# comms_sys_schematic_R2.net
KiCad netlist of a schematic drawn in EAGLE
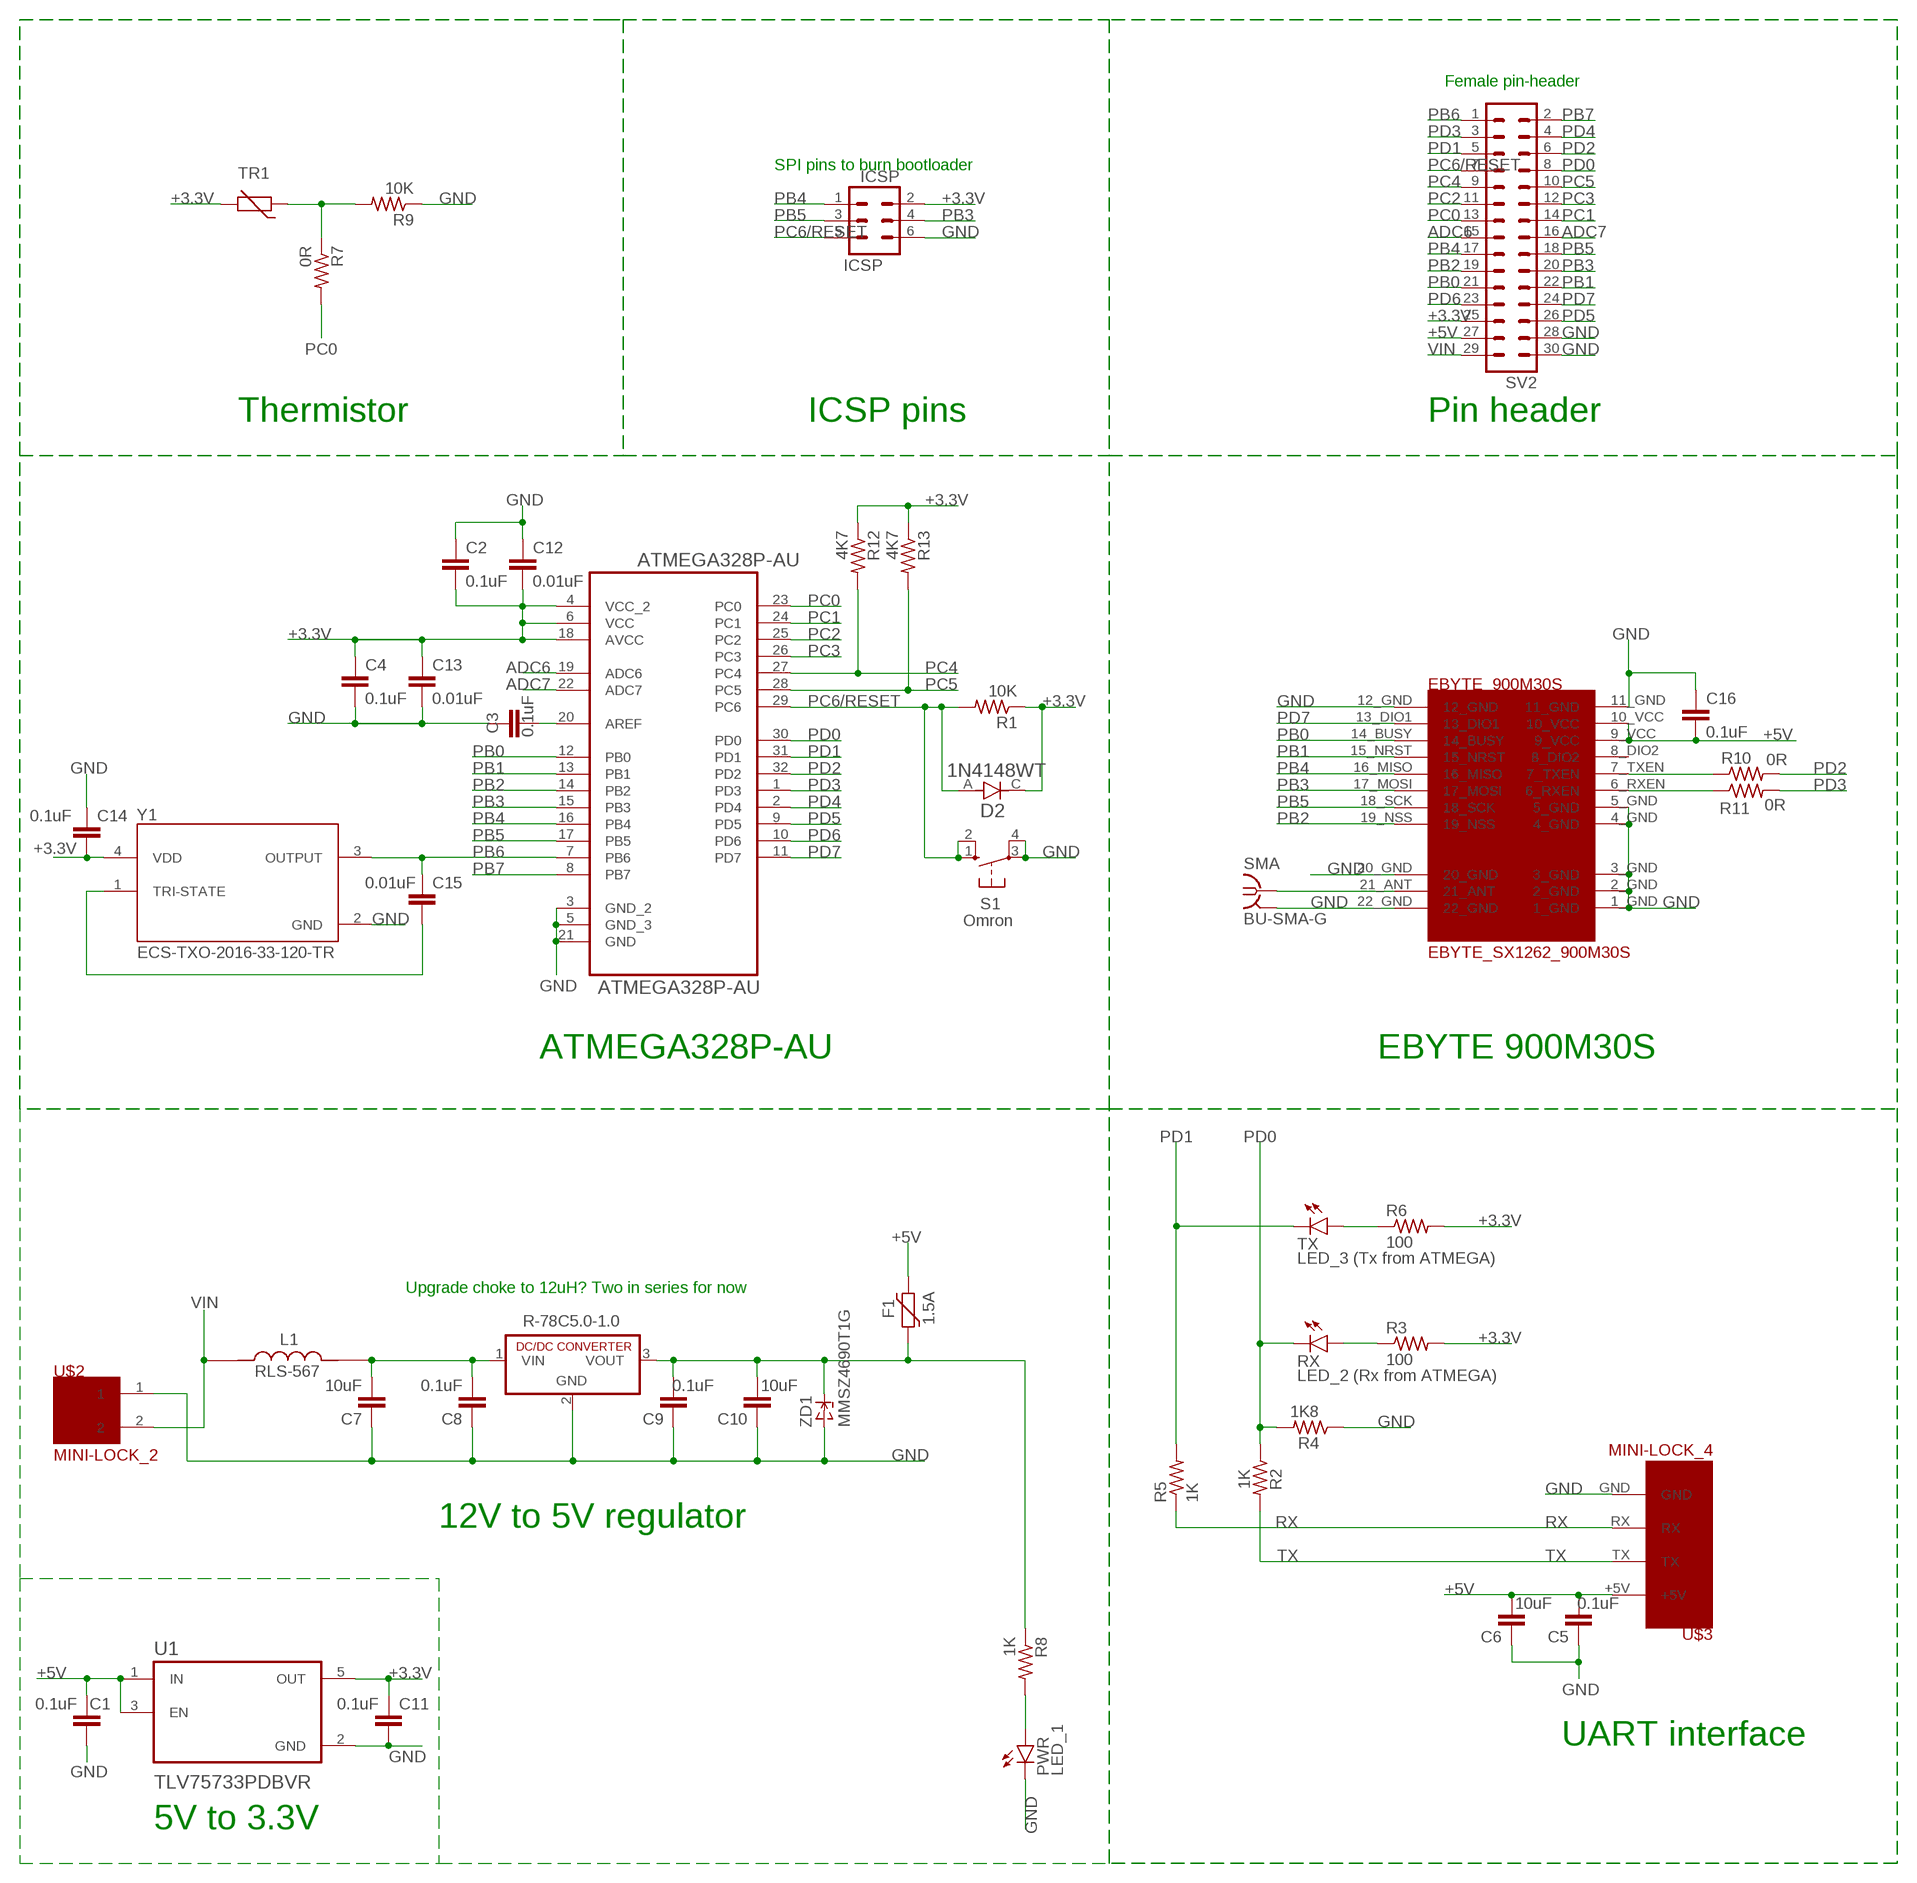
[diagram p0: schematic, sheet 1]

(export (version "E")
  (design (tool "Eeschema 10.0.6"))
  (components
    (comp (ref "ATMEGA328P-AU")
      (value "ATMEGA328P-AU")
      (footprint "eagle-import:QFP80P900X900X120-32N")
      (libsource (lib "eagle-import") (part "ATMEGA328P-AU"))
    )
    (comp (ref "C1")
      (value "0.1uF")
      (footprint "eagle-import:C0805")
      (libsource (lib "eagle-import") (part "C-EUC0805"))
    )
    (comp (ref "C2")
      (value "0.1uF")
      (footprint "eagle-import:C0805")
      (libsource (lib "eagle-import") (part "C-EUC0805"))
    )
    (comp (ref "C3")
      (value "0.1uF")
      (footprint "eagle-import:C0805")
      (libsource (lib "eagle-import") (part "C-EUC0805"))
    )
    (comp (ref "C4")
      (value "0.1uF")
      (footprint "eagle-import:C0805")
      (libsource (lib "eagle-import") (part "C-EUC0805"))
    )
    (comp (ref "C5")
      (value "0.1uF")
      (footprint "eagle-import:C0805")
      (libsource (lib "eagle-import") (part "C-EUC0805"))
    )
    (comp (ref "C6")
      (value "10uF")
      (footprint "eagle-import:C0805")
      (libsource (lib "eagle-import") (part "C-EUC0805"))
    )
    (comp (ref "C7")
      (value "10uF")
      (footprint "eagle-import:C0805")
      (libsource (lib "eagle-import") (part "C-EUC0805"))
    )
    (comp (ref "C8")
      (value "0.1uF")
      (footprint "eagle-import:C0805")
      (libsource (lib "eagle-import") (part "C-EUC0805"))
    )
    (comp (ref "C9")
      (value "0.1uF")
      (footprint "eagle-import:C0805")
      (libsource (lib "eagle-import") (part "C-EUC0805"))
    )
    (comp (ref "C10")
      (value "10uF")
      (footprint "eagle-import:C0805")
      (libsource (lib "eagle-import") (part "C-EUC0805"))
    )
    (comp (ref "C11")
      (value "0.1uF")
      (footprint "eagle-import:C0805")
      (libsource (lib "eagle-import") (part "C-EUC0805"))
    )
    (comp (ref "C12")
      (value "0.01uF")
      (footprint "eagle-import:C0805")
      (libsource (lib "eagle-import") (part "C-EUC0805"))
    )
    (comp (ref "C13")
      (value "0.01uF")
      (footprint "eagle-import:C0805")
      (libsource (lib "eagle-import") (part "C-EUC0805"))
    )
    (comp (ref "C14")
      (value "0.1uF")
      (footprint "eagle-import:C0805")
      (libsource (lib "eagle-import") (part "C-EUC0805"))
    )
    (comp (ref "C15")
      (value "0.01uF")
      (footprint "eagle-import:C0805")
      (libsource (lib "eagle-import") (part "C-EUC0805"))
    )
    (comp (ref "C16")
      (value "0.1uF")
      (footprint "eagle-import:C0805")
      (libsource (lib "eagle-import") (part "C-EUC0805"))
    )
    (comp (ref "D2")
      (value "1N4148WT")
      (footprint "eagle-import:SODFL1608X70N")
      (fields (field (name "DIGI-KEY_PART_NUMBER") "1N4148WTCT-ND") (field (name "MF") "ON Semiconductor"))
      (libsource (lib "eagle-import") (part "1N4148WT"))
    )
    (comp (ref "EBYTE_900M30S")
      (value "EBYTE_SX1262_900M30S")
      (footprint "eagle-import:EBYTE_SX1262_900M30S_FOOTPRINT")
      (libsource (lib "eagle-import") (part "EBYTE_SX1262_900M30S"))
    )
    (comp (ref "F1")
      (value "1.5A")
      (footprint "eagle-import:PTC0805")
      (libsource (lib "eagle-import") (part "FUSE_PTC-0805"))
    )
    (comp (ref "ICSP")
      (value "ICSP")
      (footprint "eagle-import:MA03-2")
      (libsource (lib "eagle-import") (part "MA03-2"))
    )
    (comp (ref "L1")
      (value "RLS-567")
      (footprint "eagle-import:IND_RLS-567")
      (fields (field (name "MF") "Recom Power"))
      (libsource (lib "eagle-import") (part "RLS-567"))
    )
    (comp (ref "PWR")
      (value "LED_1")
      (footprint "eagle-import:CHIP-LED0805")
      (libsource (lib "eagle-import") (part "LEDCHIP-LED0805"))
    )
    (comp (ref "R-78C5.0-1.0")
      (value "R-78C5.0-1.0")
      (footprint "eagle-import:SIP3")
      (libsource (lib "eagle-import") (part "R-78C-1.05.0"))
    )
    (comp (ref "R1")
      (value "10K")
      (footprint "eagle-import:R0805")
      (libsource (lib "eagle-import") (part "R-US_R0805"))
    )
    (comp (ref "R2")
      (value "1K")
      (footprint "eagle-import:R0805")
      (libsource (lib "eagle-import") (part "R-US_R0805"))
    )
    (comp (ref "R3")
      (value "100")
      (footprint "eagle-import:R0805")
      (libsource (lib "eagle-import") (part "R-US_R0805"))
    )
    (comp (ref "R4")
      (value "1K8")
      (footprint "eagle-import:R0805")
      (libsource (lib "eagle-import") (part "R-US_R0805"))
    )
    (comp (ref "R5")
      (value "1K")
      (footprint "eagle-import:R0805")
      (libsource (lib "eagle-import") (part "R-US_R0805"))
    )
    (comp (ref "R6")
      (value "100")
      (footprint "eagle-import:R0805")
      (libsource (lib "eagle-import") (part "R-US_R0805"))
    )
    (comp (ref "R7")
      (value "0R")
      (footprint "eagle-import:R0805")
      (libsource (lib "eagle-import") (part "R-US_R0805"))
    )
    (comp (ref "R8")
      (value "1K")
      (footprint "eagle-import:R0805")
      (libsource (lib "eagle-import") (part "R-US_R0805"))
    )
    (comp (ref "R9")
      (value "10K")
      (footprint "eagle-import:R0805")
      (libsource (lib "eagle-import") (part "R-US_R0805"))
    )
    (comp (ref "R10")
      (value "0R")
      (footprint "eagle-import:R0805")
      (libsource (lib "eagle-import") (part "R-US_R0805"))
    )
    (comp (ref "R11")
      (value "0R")
      (footprint "eagle-import:R0805")
      (libsource (lib "eagle-import") (part "R-US_R0805"))
    )
    (comp (ref "R12")
      (value "4K7")
      (footprint "eagle-import:R0805")
      (libsource (lib "eagle-import") (part "R-US_R0805"))
    )
    (comp (ref "R13")
      (value "4K7")
      (footprint "eagle-import:R0805")
      (libsource (lib "eagle-import") (part "R-US_R0805"))
    )
    (comp (ref "RX")
      (value "LED_2 (Rx from ATMEGA)")
      (footprint "eagle-import:CHIP-LED0805")
      (libsource (lib "eagle-import") (part "LEDCHIP-LED0805"))
    )
    (comp (ref "S1")
      (value "Omron")
      (footprint "eagle-import:B3F-10XX")
      (fields (field (name "MPN") "B3F-1000"))
      (libsource (lib "eagle-import") (part "10-XX"))
    )
    (comp (ref "SMA")
      (value "BU-SMA-G")
      (footprint "eagle-import:BU-SMA-G")
      (libsource (lib "eagle-import") (part "BU-SMA-G"))
    )
    (comp (ref "SV2")
      (value "MA15-2")
      (footprint "eagle-import:MA15-2")
      (libsource (lib "eagle-import") (part "MA15-2"))
    )
    (comp (ref "TR1")
      (value "THERMISTOR_R-2,5")
      (footprint "eagle-import:RS-2,5")
      (libsource (lib "eagle-import") (part "THERMISTOR_R-2,5"))
    )
    (comp (ref "TX")
      (value "LED_3 (Tx from ATMEGA)")
      (footprint "eagle-import:CHIP-LED0805")
      (libsource (lib "eagle-import") (part "LEDCHIP-LED0805"))
    )
    (comp (ref "U$2")
      (value "MINI-LOCK_2")
      (footprint "eagle-import:MINI-LOCK_2")
      (libsource (lib "eagle-import") (part "MINI-LOCK_2"))
    )
    (comp (ref "U$3")
      (value "MINI-LOCK_4")
      (footprint "eagle-import:MINI-LOCK_4")
      (libsource (lib "eagle-import") (part "MINI-LOCK_4"))
    )
    (comp (ref "U1")
      (value "TLV75733PDBVR")
      (footprint "eagle-import:SOT95P280X145-5N")
      (fields (field (name "DIGI-KEY_PART_NUMBER") "296-50414-1-ND") (field (name "MF") "Texas Instruments"))
      (libsource (lib "eagle-import") (part "TLV75733PDBVR"))
    )
    (comp (ref "Y1")
      (value "ECS-TXO-2016-33-120-TR")
      (footprint "eagle-import:OSC_ECS-TXO-2016-33-120-TR")
      (fields (field (name "DIGI-KEY_PART_NUMBER") "XC3160CT-ND") (field (name "MF") "ECS Inc."))
      (libsource (lib "eagle-import") (part "ECS-TXO-2016-33-120-TR"))
    )
    (comp (ref "ZD1")
      (value "MMSZ4690T1G")
      (footprint "eagle-import:SOD-123")
      (libsource (lib "eagle-import") (part "ZENERSOD-123"))
    )
  )
  (nets
    (net (code "1") (name "/+3.3V") (class "Default")
      (node (ref "ATMEGA328P-AU") (pin "18") (pinfunction "AVCC_18") (pintype "power_in"))
      (node (ref "ATMEGA328P-AU") (pin "4") (pinfunction "VCC_2_4") (pintype "power_in"))
      (node (ref "ATMEGA328P-AU") (pin "6") (pinfunction "VCC_6") (pintype "power_in"))
      (node (ref "C11") (pin "2") (pinfunction "2_2") (pintype "passive"))
      (node (ref "C12") (pin "2") (pinfunction "2_2") (pintype "passive"))
      (node (ref "C13") (pin "1") (pinfunction "1_1") (pintype "passive"))
      (node (ref "C14") (pin "2") (pinfunction "2_2") (pintype "passive"))
      (node (ref "C2") (pin "2") (pinfunction "2_2") (pintype "passive"))
      (node (ref "C4") (pin "1") (pinfunction "1_1") (pintype "passive"))
      (node (ref "D2") (pin "C") (pinfunction "C_C") (pintype "passive"))
      (node (ref "ICSP") (pin "2") (pinfunction "2_2") (pintype "passive"))
      (node (ref "R1") (pin "1") (pinfunction "1_1") (pintype "passive"))
      (node (ref "R12") (pin "1") (pinfunction "1_1") (pintype "passive"))
      (node (ref "R13") (pin "1") (pinfunction "1_1") (pintype "passive"))
      (node (ref "R3") (pin "2") (pinfunction "2_2") (pintype "passive"))
      (node (ref "R6") (pin "2") (pinfunction "2_2") (pintype "passive"))
      (node (ref "SV2") (pin "25") (pinfunction "29_25") (pintype "passive"))
      (node (ref "TR1") (pin "2") (pinfunction "2_2") (pintype "passive"))
      (node (ref "U1") (pin "5") (pinfunction "OUT_5") (pintype "output"))
      (node (ref "Y1") (pin "4") (pinfunction "VDD_4") (pintype "input"))
    )
    (net (code "2") (name "/+5V") (class "Default")
      (node (ref "C1") (pin "2") (pinfunction "2_2") (pintype "passive"))
      (node (ref "C16") (pin "2") (pinfunction "2_2") (pintype "passive"))
      (node (ref "C5") (pin "2") (pinfunction "2_2") (pintype "passive"))
      (node (ref "C6") (pin "2") (pinfunction "2_2") (pintype "passive"))
      (node (ref "EBYTE_900M30S") (pin "10_VCC") (pinfunction "10_VCC_10_VCC") (pintype "power_in"))
      (node (ref "EBYTE_900M30S") (pin "9_VCC") (pinfunction "9_VCC_9_VCC") (pintype "power_in"))
      (node (ref "F1") (pin "2") (pinfunction "2_2") (pintype "passive"))
      (node (ref "SV2") (pin "27") (pinfunction "31_27") (pintype "passive"))
      (node (ref "U$3") (pin "+5V") (pinfunction "+5V_+5V") (pintype "bidirectional"))
      (node (ref "U1") (pin "1") (pinfunction "IN_1") (pintype "input"))
      (node (ref "U1") (pin "3") (pinfunction "EN_3") (pintype "bidirectional"))
    )
    (net (code "3") (name "/ADC6") (class "Default")
      (node (ref "ATMEGA328P-AU") (pin "19") (pinfunction "ADC6_19") (pintype "input"))
      (node (ref "SV2") (pin "15") (pinfunction "19_15") (pintype "passive"))
    )
    (net (code "4") (name "/ADC7") (class "Default")
      (node (ref "ATMEGA328P-AU") (pin "22") (pinfunction "ADC7_22") (pintype "input"))
      (node (ref "SV2") (pin "16") (pinfunction "20_16") (pintype "passive"))
    )
    (net (code "5") (name "/GND") (class "Default")
      (node (ref "ATMEGA328P-AU") (pin "21") (pinfunction "GND_21") (pintype "passive"))
      (node (ref "ATMEGA328P-AU") (pin "3") (pinfunction "GND_2_3") (pintype "passive"))
      (node (ref "ATMEGA328P-AU") (pin "5") (pinfunction "GND_3_5") (pintype "passive"))
      (node (ref "C1") (pin "1") (pinfunction "1_1") (pintype "passive"))
      (node (ref "C10") (pin "1") (pinfunction "1_1") (pintype "passive"))
      (node (ref "C11") (pin "1") (pinfunction "1_1") (pintype "passive"))
      (node (ref "C12") (pin "1") (pinfunction "1_1") (pintype "passive"))
      (node (ref "C13") (pin "2") (pinfunction "2_2") (pintype "passive"))
      (node (ref "C14") (pin "1") (pinfunction "1_1") (pintype "passive"))
      (node (ref "C16") (pin "1") (pinfunction "1_1") (pintype "passive"))
      (node (ref "C2") (pin "1") (pinfunction "1_1") (pintype "passive"))
      (node (ref "C3") (pin "1") (pinfunction "1_1") (pintype "passive"))
      (node (ref "C4") (pin "2") (pinfunction "2_2") (pintype "passive"))
      (node (ref "C5") (pin "1") (pinfunction "1_1") (pintype "passive"))
      (node (ref "C6") (pin "1") (pinfunction "1_1") (pintype "passive"))
      (node (ref "C7") (pin "1") (pinfunction "1_1") (pintype "passive"))
      (node (ref "C8") (pin "1") (pinfunction "1_1") (pintype "passive"))
      (node (ref "C9") (pin "1") (pinfunction "1_1") (pintype "passive"))
      (node (ref "EBYTE_900M30S") (pin "11_GND") (pinfunction "11_GND_11_GND") (pintype "power_in"))
      (node (ref "EBYTE_900M30S") (pin "12_GND") (pinfunction "12_GND_12_GND") (pintype "power_in"))
      (node (ref "EBYTE_900M30S") (pin "1_GND") (pinfunction "1_GND_1_GND") (pintype "power_in"))
      (node (ref "EBYTE_900M30S") (pin "20_GND") (pinfunction "20_GND_20_GND") (pintype "power_in"))
      (node (ref "EBYTE_900M30S") (pin "22_GND") (pinfunction "22_GND_22_GND") (pintype "power_in"))
      (node (ref "EBYTE_900M30S") (pin "2_GND") (pinfunction "2_GND_2_GND") (pintype "power_in"))
      (node (ref "EBYTE_900M30S") (pin "3_GND") (pinfunction "3_GND_3_GND") (pintype "power_in"))
      (node (ref "EBYTE_900M30S") (pin "4_GND") (pinfunction "4_GND_4_GND") (pintype "power_in"))
      (node (ref "EBYTE_900M30S") (pin "5_GND") (pinfunction "5_GND_5_GND") (pintype "power_in"))
      (node (ref "ICSP") (pin "6") (pinfunction "6_6") (pintype "passive"))
      (node (ref "PWR") (pin "C") (pinfunction "C_C") (pintype "passive"))
      (node (ref "R-78C5.0-1.0") (pin "2") (pinfunction "GND_2") (pintype "passive"))
      (node (ref "R4") (pin "1") (pinfunction "1_1") (pintype "passive"))
      (node (ref "R9") (pin "1") (pinfunction "1_1") (pintype "passive"))
      (node (ref "S1") (pin "3") (pinfunction "P_3") (pintype "passive"))
      (node (ref "S1") (pin "4") (pinfunction "P1_4") (pintype "passive"))
      (node (ref "SMA") (pin "2") (pinfunction "2_2") (pintype "passive"))
      (node (ref "SMA") (pin "3") (pinfunction "2_3") (pintype "passive"))
      (node (ref "SMA") (pin "4") (pinfunction "2_4") (pintype "passive"))
      (node (ref "SMA") (pin "5") (pinfunction "2_5") (pintype "passive"))
      (node (ref "SV2") (pin "28") (pinfunction "32_28") (pintype "passive"))
      (node (ref "SV2") (pin "30") (pinfunction "34_30") (pintype "passive"))
      (node (ref "U$2") (pin "1") (pinfunction "1_1") (pintype "bidirectional"))
      (node (ref "U$3") (pin "GND") (pinfunction "GND_GND") (pintype "bidirectional"))
      (node (ref "U1") (pin "2") (pinfunction "GND_2") (pintype "power_in"))
      (node (ref "Y1") (pin "2") (pinfunction "GND_2") (pintype "power_in"))
      (node (ref "ZD1") (pin "A") (pinfunction "A_A") (pintype "passive"))
    )
    (net (code "6") (name "/PB0") (class "Default")
      (node (ref "ATMEGA328P-AU") (pin "12") (pinfunction "PB0_12") (pintype "bidirectional"))
      (node (ref "EBYTE_900M30S") (pin "14_BUSY") (pinfunction "14_BUSY_14_BUSY") (pintype "bidirectional"))
      (node (ref "SV2") (pin "21") (pinfunction "25_21") (pintype "passive"))
    )
    (net (code "7") (name "/PB1") (class "Default")
      (node (ref "ATMEGA328P-AU") (pin "13") (pinfunction "PB1_13") (pintype "bidirectional"))
      (node (ref "EBYTE_900M30S") (pin "15_NRST") (pinfunction "15_NRST_15_NRST") (pintype "bidirectional"))
      (node (ref "SV2") (pin "22") (pinfunction "26_22") (pintype "passive"))
    )
    (net (code "8") (name "/PB2") (class "Default")
      (node (ref "ATMEGA328P-AU") (pin "14") (pinfunction "PB2_14") (pintype "bidirectional"))
      (node (ref "EBYTE_900M30S") (pin "19_NSS") (pinfunction "19_NSS_19_NSS") (pintype "bidirectional"))
      (node (ref "SV2") (pin "19") (pinfunction "23_19") (pintype "passive"))
    )
    (net (code "9") (name "/PB3") (class "Default")
      (node (ref "ATMEGA328P-AU") (pin "15") (pinfunction "PB3_15") (pintype "bidirectional"))
      (node (ref "EBYTE_900M30S") (pin "17_MOSI") (pinfunction "17_MOSI_17_MOSI") (pintype "bidirectional"))
      (node (ref "ICSP") (pin "4") (pinfunction "4_4") (pintype "passive"))
      (node (ref "SV2") (pin "20") (pinfunction "24_20") (pintype "passive"))
    )
    (net (code "10") (name "/PB4") (class "Default")
      (node (ref "ATMEGA328P-AU") (pin "16") (pinfunction "PB4_16") (pintype "bidirectional"))
      (node (ref "EBYTE_900M30S") (pin "16_MISO") (pinfunction "16_MISO_16_MISO") (pintype "bidirectional"))
      (node (ref "ICSP") (pin "1") (pinfunction "1_1") (pintype "passive"))
      (node (ref "SV2") (pin "17") (pinfunction "21_17") (pintype "passive"))
    )
    (net (code "11") (name "/PB5") (class "Default")
      (node (ref "ATMEGA328P-AU") (pin "17") (pinfunction "PB5_17") (pintype "bidirectional"))
      (node (ref "EBYTE_900M30S") (pin "18_SCK") (pinfunction "18_SCK_18_SCK") (pintype "bidirectional"))
      (node (ref "ICSP") (pin "3") (pinfunction "3_3") (pintype "passive"))
      (node (ref "SV2") (pin "18") (pinfunction "22_18") (pintype "passive"))
    )
    (net (code "12") (name "/PB6") (class "Default")
      (node (ref "ATMEGA328P-AU") (pin "7") (pinfunction "PB6_7") (pintype "bidirectional"))
      (node (ref "C15") (pin "1") (pinfunction "1_1") (pintype "passive"))
      (node (ref "SV2") (pin "1") (pinfunction "5_1") (pintype "passive"))
      (node (ref "Y1") (pin "3") (pinfunction "OUTPUT_3") (pintype "output"))
    )
    (net (code "13") (name "/PB7") (class "Default")
      (node (ref "ATMEGA328P-AU") (pin "8") (pinfunction "PB7_8") (pintype "bidirectional"))
      (node (ref "SV2") (pin "2") (pinfunction "6_2") (pintype "passive"))
    )
    (net (code "14") (name "/PC0") (class "Default")
      (node (ref "ATMEGA328P-AU") (pin "23") (pinfunction "PC0_23") (pintype "bidirectional"))
      (node (ref "R7") (pin "2") (pinfunction "2_2") (pintype "passive"))
      (node (ref "SV2") (pin "13") (pinfunction "17_13") (pintype "passive"))
    )
    (net (code "15") (name "/PC1") (class "Default")
      (node (ref "ATMEGA328P-AU") (pin "24") (pinfunction "PC1_24") (pintype "bidirectional"))
      (node (ref "SV2") (pin "14") (pinfunction "18_14") (pintype "passive"))
    )
    (net (code "16") (name "/PC2") (class "Default")
      (node (ref "ATMEGA328P-AU") (pin "25") (pinfunction "PC2_25") (pintype "bidirectional"))
      (node (ref "SV2") (pin "11") (pinfunction "15_11") (pintype "passive"))
    )
    (net (code "17") (name "/PC3") (class "Default")
      (node (ref "ATMEGA328P-AU") (pin "26") (pinfunction "PC3_26") (pintype "bidirectional"))
      (node (ref "SV2") (pin "12") (pinfunction "16_12") (pintype "passive"))
    )
    (net (code "18") (name "/PC4") (class "Default")
      (node (ref "ATMEGA328P-AU") (pin "27") (pinfunction "PC4_27") (pintype "bidirectional"))
      (node (ref "R12") (pin "2") (pinfunction "2_2") (pintype "passive"))
      (node (ref "SV2") (pin "9") (pinfunction "13_9") (pintype "passive"))
    )
    (net (code "19") (name "/PC5") (class "Default")
      (node (ref "ATMEGA328P-AU") (pin "28") (pinfunction "PC5_28") (pintype "bidirectional"))
      (node (ref "R13") (pin "2") (pinfunction "2_2") (pintype "passive"))
      (node (ref "SV2") (pin "10") (pinfunction "14_10") (pintype "passive"))
    )
    (net (code "20") (name "/PC6{slash}RESET") (class "Default")
      (node (ref "ATMEGA328P-AU") (pin "29") (pinfunction "PC6_29") (pintype "bidirectional"))
      (node (ref "D2") (pin "A") (pinfunction "A_A") (pintype "passive"))
      (node (ref "ICSP") (pin "5") (pinfunction "5_5") (pintype "passive"))
      (node (ref "R1") (pin "2") (pinfunction "2_2") (pintype "passive"))
      (node (ref "S1") (pin "1") (pinfunction "S_1") (pintype "passive"))
      (node (ref "S1") (pin "2") (pinfunction "S1_2") (pintype "passive"))
      (node (ref "SV2") (pin "7") (pinfunction "11_7") (pintype "passive"))
    )
    (net (code "21") (name "/PD0") (class "Default")
      (node (ref "ATMEGA328P-AU") (pin "30") (pinfunction "PD0_30") (pintype "bidirectional"))
      (node (ref "R2") (pin "1") (pinfunction "1_1") (pintype "passive"))
      (node (ref "R4") (pin "2") (pinfunction "2_2") (pintype "passive"))
      (node (ref "RX") (pin "C") (pinfunction "C_C") (pintype "passive"))
      (node (ref "SV2") (pin "8") (pinfunction "12_8") (pintype "passive"))
    )
    (net (code "22") (name "/PD1") (class "Default")
      (node (ref "ATMEGA328P-AU") (pin "31") (pinfunction "PD1_31") (pintype "bidirectional"))
      (node (ref "R5") (pin "2") (pinfunction "2_2") (pintype "passive"))
      (node (ref "SV2") (pin "5") (pinfunction "9_5") (pintype "passive"))
      (node (ref "TX") (pin "C") (pinfunction "C_C") (pintype "passive"))
    )
    (net (code "23") (name "/PD2") (class "Default")
      (node (ref "ATMEGA328P-AU") (pin "32") (pinfunction "PD2_32") (pintype "bidirectional"))
      (node (ref "R10") (pin "2") (pinfunction "2_2") (pintype "passive"))
      (node (ref "SV2") (pin "6") (pinfunction "10_6") (pintype "passive"))
    )
    (net (code "24") (name "/PD3") (class "Default")
      (node (ref "ATMEGA328P-AU") (pin "1") (pinfunction "PD3_1") (pintype "bidirectional"))
      (node (ref "R11") (pin "2") (pinfunction "2_2") (pintype "passive"))
      (node (ref "SV2") (pin "3") (pinfunction "7_3") (pintype "passive"))
    )
    (net (code "25") (name "/PD4") (class "Default")
      (node (ref "ATMEGA328P-AU") (pin "2") (pinfunction "PD4_2") (pintype "bidirectional"))
      (node (ref "SV2") (pin "4") (pinfunction "8_4") (pintype "passive"))
    )
    (net (code "26") (name "/PD5") (class "Default")
      (node (ref "ATMEGA328P-AU") (pin "9") (pinfunction "PD5_9") (pintype "bidirectional"))
      (node (ref "SV2") (pin "26") (pinfunction "30_26") (pintype "passive"))
    )
    (net (code "27") (name "/PD6") (class "Default")
      (node (ref "ATMEGA328P-AU") (pin "10") (pinfunction "PD6_10") (pintype "bidirectional"))
      (node (ref "SV2") (pin "23") (pinfunction "27_23") (pintype "passive"))
    )
    (net (code "28") (name "/PD7") (class "Default")
      (node (ref "ATMEGA328P-AU") (pin "11") (pinfunction "PD7_11") (pintype "bidirectional"))
      (node (ref "EBYTE_900M30S") (pin "13_DIO1") (pinfunction "13_DIO1_13_DIO1") (pintype "bidirectional"))
      (node (ref "SV2") (pin "24") (pinfunction "28_24") (pintype "passive"))
    )
    (net (code "29") (name "/RX") (class "Default")
      (node (ref "R5") (pin "1") (pinfunction "1_1") (pintype "passive"))
      (node (ref "U$3") (pin "RX") (pinfunction "RX_RX") (pintype "bidirectional"))
    )
    (net (code "30") (name "/TX") (class "Default")
      (node (ref "R2") (pin "2") (pinfunction "2_2") (pintype "passive"))
      (node (ref "U$3") (pin "TX") (pinfunction "TX_TX") (pintype "bidirectional"))
    )
    (net (code "31") (name "/VIN") (class "Default")
      (node (ref "L1") (pin "1") (pinfunction "1_1") (pintype "passive"))
      (node (ref "SV2") (pin "29") (pinfunction "33_29") (pintype "passive"))
      (node (ref "U$2") (pin "2") (pinfunction "2_2") (pintype "bidirectional"))
    )
    (net (code "32") (name "Net-(ATMEGA328P-AU-AREF)") (class "Default")
      (node (ref "ATMEGA328P-AU") (pin "20") (pinfunction "AREF_20") (pintype "input"))
      (node (ref "C3") (pin "2") (pinfunction "2_2") (pintype "passive"))
    )
    (net (code "33") (name "Net-(EBYTE_900M30S-Pad6_RXEN)") (class "Default")
      (node (ref "EBYTE_900M30S") (pin "6_RXEN") (pinfunction "6_RXEN_6_RXEN") (pintype "bidirectional"))
      (node (ref "R11") (pin "1") (pinfunction "1_1") (pintype "passive"))
    )
    (net (code "34") (name "Net-(EBYTE_900M30S-Pad7_TXEN)") (class "Default")
      (node (ref "EBYTE_900M30S") (pin "7_TXEN") (pinfunction "7_TXEN_7_TXEN") (pintype "bidirectional"))
      (node (ref "R10") (pin "1") (pinfunction "1_1") (pintype "passive"))
    )
    (net (code "35") (name "Net-(EBYTE_900M30S-Pad21_ANT)") (class "Default")
      (node (ref "EBYTE_900M30S") (pin "21_ANT") (pinfunction "21_ANT_21_ANT") (pintype "bidirectional"))
      (node (ref "SMA") (pin "1") (pinfunction "1_1") (pintype "passive"))
    )
    (net (code "36") (name "Net-(PWR-PadA)") (class "Default")
      (node (ref "PWR") (pin "A") (pinfunction "A_A") (pintype "passive"))
      (node (ref "R8") (pin "2") (pinfunction "2_2") (pintype "passive"))
    )
    (net (code "37") (name "Net-(R-78C5.0-1.0-VIN)") (class "Default")
      (node (ref "C7") (pin "2") (pinfunction "2_2") (pintype "passive"))
      (node (ref "C8") (pin "2") (pinfunction "2_2") (pintype "passive"))
      (node (ref "L1") (pin "2") (pinfunction "2_2") (pintype "passive"))
      (node (ref "R-78C5.0-1.0") (pin "1") (pinfunction "VIN_1") (pintype "passive"))
    )
    (net (code "38") (name "Net-(R-78C5.0-1.0-VOUT)") (class "Default")
      (node (ref "C10") (pin "2") (pinfunction "2_2") (pintype "passive"))
      (node (ref "C9") (pin "2") (pinfunction "2_2") (pintype "passive"))
      (node (ref "F1") (pin "1") (pinfunction "1_1") (pintype "passive"))
      (node (ref "R-78C5.0-1.0") (pin "3") (pinfunction "VOUT_3") (pintype "passive"))
      (node (ref "R8") (pin "1") (pinfunction "1_1") (pintype "passive"))
      (node (ref "ZD1") (pin "C") (pinfunction "C_C") (pintype "passive"))
    )
    (net (code "39") (name "Net-(R3-Pad1)") (class "Default")
      (node (ref "R3") (pin "1") (pinfunction "1_1") (pintype "passive"))
      (node (ref "RX") (pin "A") (pinfunction "A_A") (pintype "passive"))
    )
    (net (code "40") (name "Net-(R6-Pad1)") (class "Default")
      (node (ref "R6") (pin "1") (pinfunction "1_1") (pintype "passive"))
      (node (ref "TX") (pin "A") (pinfunction "A_A") (pintype "passive"))
    )
    (net (code "41") (name "Net-(R7-Pad1)") (class "Default")
      (node (ref "R7") (pin "1") (pinfunction "1_1") (pintype "passive"))
      (node (ref "R9") (pin "2") (pinfunction "2_2") (pintype "passive"))
      (node (ref "TR1") (pin "1") (pinfunction "1_1") (pintype "passive"))
    )
    (net (code "42") (name "Net-(Y1-TRI-STATE)") (class "Default")
      (node (ref "C15") (pin "2") (pinfunction "2_2") (pintype "passive"))
      (node (ref "Y1") (pin "1") (pinfunction "TRI-STATE_1") (pintype "input"))
    )
    (net (code "43") (name "unconnected-(EBYTE_900M30S-Pad8_DIO2)") (class "Default")
      (node (ref "EBYTE_900M30S") (pin "8_DIO2") (pinfunction "8_DIO2_8_DIO2") (pintype "bidirectional"))
    )
  )
)
